# 3_waffling60-MXHS-ISO_mcu.net
KiCad netlist of a schematic drawn in Altium Designer
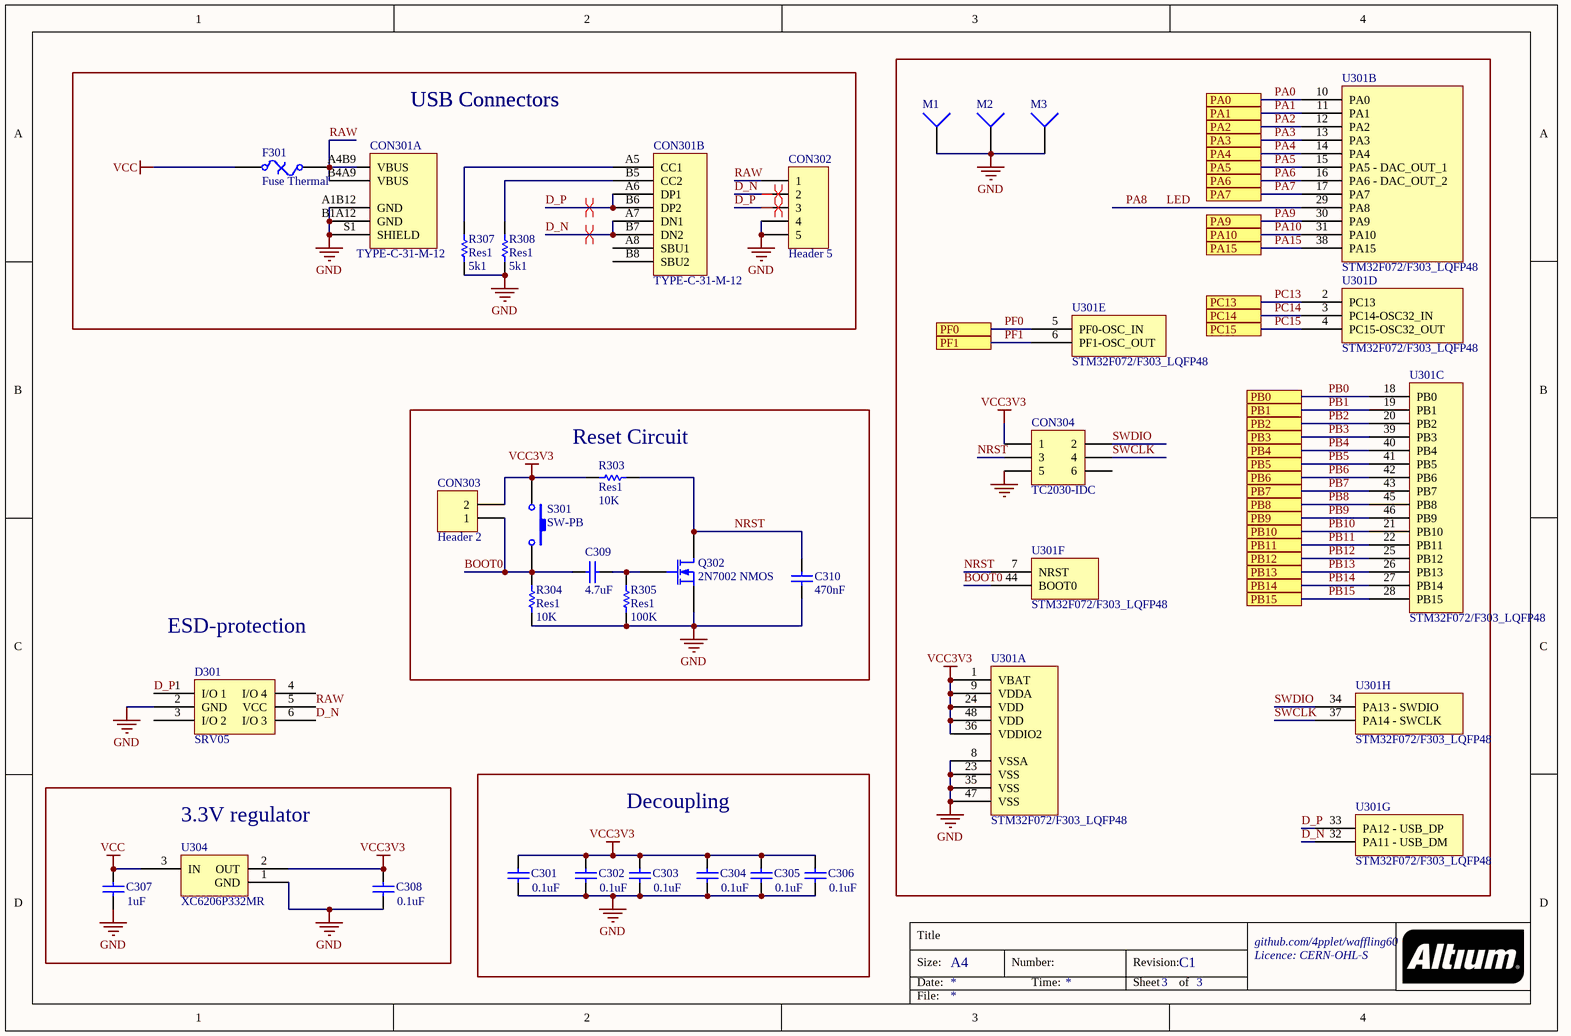
[diagram p0: 3_waffling60-MXHS-ISO_mcu.SchDoc]

(export (version "E")
  (design (tool "Eeschema 10.0.6"))
  (components
    (comp (ref "C301")
      (value "0.1uF")
      (footprint "C0603[1608]")
      (description "Capacitor")
      (fields (field (name "MFG") "KEMET") (field (name "LCSC PART #") "C14663"))
      (libsource (lib "Miscellaneous Devices") (part "Cap"))
    )
    (comp (ref "C302")
      (value "0.1uF")
      (footprint "C0603[1608]")
      (description "Capacitor")
      (fields (field (name "MFG") "KEMET") (field (name "LCSC PART #") "C14663"))
      (libsource (lib "Miscellaneous Devices") (part "Cap"))
    )
    (comp (ref "C303")
      (value "0.1uF")
      (footprint "C0603[1608]")
      (description "Capacitor")
      (fields (field (name "MFG") "KEMET") (field (name "LCSC PART #") "C14663"))
      (libsource (lib "Miscellaneous Devices") (part "Cap"))
    )
    (comp (ref "C304")
      (value "0.1uF")
      (footprint "C0603[1608]")
      (description "Capacitor")
      (fields (field (name "MFG") "KEMET") (field (name "LCSC PART #") "C14663"))
      (libsource (lib "Miscellaneous Devices") (part "Cap"))
    )
    (comp (ref "C305")
      (value "0.1uF")
      (footprint "C0603[1608]")
      (description "Capacitor")
      (fields (field (name "MFG") "KEMET") (field (name "LCSC PART #") "C14663"))
      (libsource (lib "Miscellaneous Devices") (part "Cap"))
    )
    (comp (ref "C306")
      (value "0.1uF")
      (footprint "C0603[1608]")
      (description "Capacitor")
      (fields (field (name "MFG") "KEMET") (field (name "LCSC PART #") "C14663"))
      (libsource (lib "Miscellaneous Devices") (part "Cap"))
    )
    (comp (ref "C307")
      (value "1uF")
      (footprint "C0603[1608]")
      (description "Capacitor")
      (fields (field (name "LCSC PART #") "C15849") (field (name "MRF.PART") "CL10A105KB8NNNC"))
      (libsource (lib "Miscellaneous Devices") (part "Cap"))
    )
    (comp (ref "C308")
      (value "0.1uF")
      (footprint "C0603[1608]")
      (description "Capacitor")
      (fields (field (name "MFG") "KEMET") (field (name "LCSC PART #") "C14663"))
      (libsource (lib "Miscellaneous Devices") (part "Cap"))
    )
    (comp (ref "C309")
      (value "4.7uF")
      (footprint "C0603[1608]")
      (description "Capacitor")
      (fields (field (name "LCSC PART #") "C19666"))
      (libsource (lib "Miscellaneous Devices") (part "Cap"))
    )
    (comp (ref "C310")
      (value "470nF")
      (footprint "C0603[1608]")
      (description "Capacitor")
      (fields (field (name "MFG") "KEMET") (field (name "LCSC PART #") "C14663"))
      (libsource (lib "Miscellaneous Devices") (part "Cap"))
    )
    (comp (ref "CON301")
      (value "TYPE-C-31-M-12")
      (footprint "TYPE-C-31-M-12")
      (fields (field (name "MFG") "Korean Hroparts Elec") (field (name "LCSC PART #") "C165948"))
      (libsource (lib "Schlib1") (part "TYPE-C-31-M-12"))
    )
    (comp (ref "CON302")
      (value "Header 5")
      (footprint "JST SM04B-SRSS-TB")
      (description "JST for USB daughter board")
      (fields (field (name "MFG") "JST Sales America Inc.") (field (name "LCSC PART #") "C160404"))
      (libsource (lib "Miscellaneous Connectors") (part "Header 5"))
    )
    (comp (ref "CON303")
      (value "Header 2")
      (footprint "HDR1X2")
      (description "Header, 2-Pin")
      (libsource (lib "Miscellaneous Connectors") (part "Header 2"))
    )
    (comp (ref "CON304")
      (value "TC2030-IDC")
      (footprint "TC2030-IDC-NL")
      (description "Header, 3-Pin, Dual row")
      (libsource (lib "Miscellaneous Connectors") (part "Header 3X2"))
    )
    (comp (ref "D301")
      (value "SRV05")
      (footprint "SOT-23-6")
      (fields (field (name "LCSC PART #") "C85364") (field (name "MRF.PART") "SRV05-4-P-T7"))
      (libsource (lib "Keebs") (part "SRV05"))
    )
    (comp (ref "F301")
      (value "Fuse Thermal")
      (footprint "C1206[3216]")
      (description "Thermal Fuse")
      (fields (field (name "MFG") "Bel Fuse Inc.") (field (name "LCSC PART #") "C135338"))
      (libsource (lib "Miscellaneous Devices") (part "Fuse Thermal"))
    )
    (comp (ref "M1")
      (value "Socket")
      (footprint "mounting_hole")
      (libsource (lib "Miscellaneous Connectors") (part "Socket"))
    )
    (comp (ref "M2")
      (value "Socket")
      (footprint "mounting_hole")
      (libsource (lib "Miscellaneous Connectors") (part "Socket"))
    )
    (comp (ref "M3")
      (value "Socket")
      (footprint "mounting_hole")
      (libsource (lib "Miscellaneous Connectors") (part "Socket"))
    )
    (comp (ref "Q302")
      (value "2N7002 NMOS")
      (footprint "SOT-23-3")
      (description "N-Channel MOSFET")
      (fields (field (name "LCSC PART #") "C8545") (field (name "MRF.PART") "2N7002"))
      (libsource (lib "Miscellaneous Devices") (part "MOSFET-N"))
    )
    (comp (ref "R303")
      (value "Res1")
      (footprint "R0603[1608]")
      (description "Resistor")
      (fields
        (field (name "ALTIUM_VALUE") "10K")
        (field (name "MFG") "Panasonic Electronic Components")
        (field (name "LCSC PART #") "C25804")
      )
      (libsource (lib "Miscellaneous Devices") (part "Res1"))
    )
    (comp (ref "R304")
      (value "Res1")
      (footprint "R0603[1608]")
      (description "Resistor")
      (fields
        (field (name "ALTIUM_VALUE") "10K")
        (field (name "MFG") "Panasonic Electronic Components")
        (field (name "LCSC PART #") "C25804")
      )
      (libsource (lib "Miscellaneous Devices") (part "Res1"))
    )
    (comp (ref "R305")
      (value "Res1")
      (footprint "R0603[1608]")
      (description "Resistor")
      (fields
        (field (name "ALTIUM_VALUE") "100K")
        (field (name "LCSC PART #") "C25803")
        (field (name "MRF.PART") "0603WAF1003T5E")
      )
      (libsource (lib "Miscellaneous Devices") (part "Res1"))
    )
    (comp (ref "R307")
      (value "Res1")
      (footprint "R0603[1608]")
      (description "Resistor")
      (fields
        (field (name "ALTIUM_VALUE") "5k1")
        (field (name "MFG") "Panasonic Electronic Components")
        (field (name "LCSC PART #") "C23186")
      )
      (libsource (lib "Miscellaneous Devices") (part "Res1"))
    )
    (comp (ref "R308")
      (value "Res1")
      (footprint "R0603[1608]")
      (description "Resistor")
      (fields
        (field (name "ALTIUM_VALUE") "5k1")
        (field (name "MFG") "Panasonic Electronic Components")
        (field (name "LCSC PART #") "C23186")
      )
      (libsource (lib "Miscellaneous Devices") (part "Res1"))
    )
    (comp (ref "S301")
      (value "SW-PB")
      (footprint "XKB Switch")
      (description "Switch")
      (fields (field (name "MFG") "C&K") (field (name "MRF.PART") "TS-1187A-C-D-B"))
      (libsource (lib "Miscellaneous Devices") (part "SW-PB"))
    )
    (comp (ref "U301")
      (value "STM32F072/F303_LQFP48")
      (footprint "STM32 - COMBO 7X7MM")
      (fields (field (name "LCSC PART #") "C915660") (field (name "MRF.PART") "APM32F072CBT6"))
      (libsource (lib "Keebs") (part "STM32F072/F303_LQFP48"))
    )
    (comp (ref "U304")
      (value "XC6206P332MR")
      (footprint "SOT-23-3")
      (fields (field (name "LCSC PART #") "C5446") (field (name "MFG") "Texas Instruments"))
      (libsource (lib "Keebs") (part "SOT23 LDO"))
    )
  )
  (nets
    (net (code "1") (name "/BOOT0") (class "Default")
      (node (ref "C309") (pin "1") (pinfunction "1_1") (pintype "passive"))
      (node (ref "CON303") (pin "1") (pinfunction "1_1") (pintype "passive"))
      (node (ref "R304") (pin "1") (pinfunction "1_1") (pintype "passive"))
      (node (ref "S301") (pin "2") (pinfunction "2_2") (pintype "passive"))
      (node (ref "U301") (pin "44") (pinfunction "BOOT0_44") (pintype "passive"))
    )
    (net (code "2") (name "/D_N") (class "Default")
      (node (ref "CON301") (pin "A7") (pinfunction "DN1_A7") (pintype "passive"))
      (node (ref "CON301") (pin "B7") (pinfunction "DN2_B7") (pintype "passive"))
      (node (ref "CON302") (pin "2") (pinfunction "2_2") (pintype "passive"))
      (node (ref "D301") (pin "6") (pinfunction "I/O_3_6") (pintype "passive"))
      (node (ref "U301") (pin "32") (pinfunction "PA11_-_USB_DM_32") (pintype "passive"))
    )
    (net (code "3") (name "/D_P") (class "Default")
      (node (ref "CON301") (pin "A6") (pinfunction "DP1_A6") (pintype "passive"))
      (node (ref "CON301") (pin "B6") (pinfunction "DP2_B6") (pintype "passive"))
      (node (ref "CON302") (pin "3") (pinfunction "3_3") (pintype "passive"))
      (node (ref "D301") (pin "1") (pinfunction "I/O_1_1") (pintype "passive"))
      (node (ref "U301") (pin "33") (pinfunction "PA12_-_USB_DP_33") (pintype "passive"))
    )
    (net (code "4") (name "/LED") (class "Default")
      (node (ref "U301") (pin "29") (pinfunction "PA8_29") (pintype "passive"))
    )
    (net (code "5") (name "/NRST") (class "Default")
      (node (ref "C310") (pin "1") (pinfunction "1_1") (pintype "passive"))
      (node (ref "CON304") (pin "3") (pinfunction "3_3") (pintype "passive"))
      (node (ref "Q302") (pin "3") (pinfunction "D_3") (pintype "passive"))
      (node (ref "R303") (pin "2") (pinfunction "2_2") (pintype "passive"))
      (node (ref "U301") (pin "7") (pinfunction "NRST_7") (pintype "passive"))
    )
    (net (code "6") (name "/PA0") (class "Default")
      (node (ref "U301") (pin "10") (pinfunction "PA0_10") (pintype "passive"))
    )
    (net (code "7") (name "/PA1") (class "Default")
      (node (ref "U301") (pin "11") (pinfunction "PA1_11") (pintype "passive"))
    )
    (net (code "8") (name "/PA2") (class "Default")
      (node (ref "U301") (pin "12") (pinfunction "PA2_12") (pintype "passive"))
    )
    (net (code "9") (name "/PA3") (class "Default")
      (node (ref "U301") (pin "13") (pinfunction "PA3_13") (pintype "passive"))
    )
    (net (code "10") (name "/PA4") (class "Default")
      (node (ref "U301") (pin "14") (pinfunction "PA4_14") (pintype "passive"))
    )
    (net (code "11") (name "/PA5") (class "Default")
      (node (ref "U301") (pin "15") (pinfunction "PA5_-_DAC_OUT_1_15") (pintype "passive"))
    )
    (net (code "12") (name "/PA6") (class "Default")
      (node (ref "U301") (pin "16") (pinfunction "PA6_-_DAC_OUT_2_16") (pintype "passive"))
    )
    (net (code "13") (name "/PA7") (class "Default")
      (node (ref "U301") (pin "17") (pinfunction "PA7_17") (pintype "passive"))
    )
    (net (code "14") (name "/PA9") (class "Default")
      (node (ref "U301") (pin "30") (pinfunction "PA9_30") (pintype "passive"))
    )
    (net (code "15") (name "/PA10") (class "Default")
      (node (ref "U301") (pin "31") (pinfunction "PA10_31") (pintype "passive"))
    )
    (net (code "16") (name "/PA15") (class "Default")
      (node (ref "U301") (pin "38") (pinfunction "PA15_38") (pintype "passive"))
    )
    (net (code "17") (name "/PB0") (class "Default")
      (node (ref "U301") (pin "18") (pinfunction "PB0_18") (pintype "passive"))
    )
    (net (code "18") (name "/PB1") (class "Default")
      (node (ref "U301") (pin "19") (pinfunction "PB1_19") (pintype "passive"))
    )
    (net (code "19") (name "/PB2") (class "Default")
      (node (ref "U301") (pin "20") (pinfunction "PB2_20") (pintype "passive"))
    )
    (net (code "20") (name "/PB3") (class "Default")
      (node (ref "U301") (pin "39") (pinfunction "PB3_39") (pintype "passive"))
    )
    (net (code "21") (name "/PB4") (class "Default")
      (node (ref "U301") (pin "40") (pinfunction "PB4_40") (pintype "passive"))
    )
    (net (code "22") (name "/PB5") (class "Default")
      (node (ref "U301") (pin "41") (pinfunction "PB5_41") (pintype "passive"))
    )
    (net (code "23") (name "/PB6") (class "Default")
      (node (ref "U301") (pin "42") (pinfunction "PB6_42") (pintype "passive"))
    )
    (net (code "24") (name "/PB7") (class "Default")
      (node (ref "U301") (pin "43") (pinfunction "PB7_43") (pintype "passive"))
    )
    (net (code "25") (name "/PB8") (class "Default")
      (node (ref "U301") (pin "45") (pinfunction "PB8_45") (pintype "passive"))
    )
    (net (code "26") (name "/PB9") (class "Default")
      (node (ref "U301") (pin "46") (pinfunction "PB9_46") (pintype "passive"))
    )
    (net (code "27") (name "/PB10") (class "Default")
      (node (ref "U301") (pin "21") (pinfunction "PB10_21") (pintype "passive"))
    )
    (net (code "28") (name "/PB11") (class "Default")
      (node (ref "U301") (pin "22") (pinfunction "PB11_22") (pintype "passive"))
    )
    (net (code "29") (name "/PB12") (class "Default")
      (node (ref "U301") (pin "25") (pinfunction "PB12_25") (pintype "passive"))
    )
    (net (code "30") (name "/PB13") (class "Default")
      (node (ref "U301") (pin "26") (pinfunction "PB13_26") (pintype "passive"))
    )
    (net (code "31") (name "/PB14") (class "Default")
      (node (ref "U301") (pin "27") (pinfunction "PB14_27") (pintype "passive"))
    )
    (net (code "32") (name "/PB15") (class "Default")
      (node (ref "U301") (pin "28") (pinfunction "PB15_28") (pintype "passive"))
    )
    (net (code "33") (name "/PC13") (class "Default")
      (node (ref "U301") (pin "2") (pinfunction "PC13_2") (pintype "passive"))
    )
    (net (code "34") (name "/PC14") (class "Default")
      (node (ref "U301") (pin "3") (pinfunction "PC14-OSC32_IN_3") (pintype "passive"))
    )
    (net (code "35") (name "/PC15") (class "Default")
      (node (ref "U301") (pin "4") (pinfunction "PC15-OSC32_OUT_4") (pintype "passive"))
    )
    (net (code "36") (name "/PF0") (class "Default")
      (node (ref "U301") (pin "5") (pinfunction "PF0-OSC_IN_5") (pintype "passive"))
    )
    (net (code "37") (name "/PF1") (class "Default")
      (node (ref "U301") (pin "6") (pinfunction "PF1-OSC_OUT_6") (pintype "passive"))
    )
    (net (code "38") (name "/RAW") (class "Default")
      (node (ref "CON301") (pin "A4B9") (pinfunction "VBUS_A4B9") (pintype "passive"))
      (node (ref "CON301") (pin "B4A9") (pinfunction "VBUS_B4A9") (pintype "passive"))
      (node (ref "CON302") (pin "1") (pinfunction "1_1") (pintype "passive"))
      (node (ref "D301") (pin "5") (pinfunction "VCC_5") (pintype "passive"))
      (node (ref "F301") (pin "2") (pinfunction "2_2") (pintype "passive"))
    )
    (net (code "39") (name "/SWCLK") (class "Default")
      (node (ref "CON304") (pin "4") (pinfunction "4_4") (pintype "passive"))
      (node (ref "U301") (pin "37") (pinfunction "PA14_-_SWCLK_37") (pintype "passive"))
    )
    (net (code "40") (name "/SWDIO") (class "Default")
      (node (ref "CON304") (pin "2") (pinfunction "2_2") (pintype "passive"))
      (node (ref "U301") (pin "34") (pinfunction "PA13_-_SWDIO_34") (pintype "passive"))
    )
    (net (code "41") (name "GND") (class "Default")
      (node (ref "C301") (pin "1") (pinfunction "1_1") (pintype "passive"))
      (node (ref "C302") (pin "1") (pinfunction "1_1") (pintype "passive"))
      (node (ref "C303") (pin "1") (pinfunction "1_1") (pintype "passive"))
      (node (ref "C304") (pin "1") (pinfunction "1_1") (pintype "passive"))
      (node (ref "C305") (pin "1") (pinfunction "1_1") (pintype "passive"))
      (node (ref "C306") (pin "1") (pinfunction "1_1") (pintype "passive"))
      (node (ref "C307") (pin "1") (pinfunction "1_1") (pintype "passive"))
      (node (ref "C308") (pin "1") (pinfunction "1_1") (pintype "passive"))
      (node (ref "C310") (pin "2") (pinfunction "2_2") (pintype "passive"))
      (node (ref "CON301") (pin "A1B12") (pinfunction "GND_A1B12") (pintype "passive"))
      (node (ref "CON301") (pin "B1A12") (pinfunction "GND_B1A12") (pintype "passive"))
      (node (ref "CON301") (pin "S1") (pinfunction "SHIELD_S1") (pintype "passive"))
      (node (ref "CON302") (pin "4") (pinfunction "4_4") (pintype "passive"))
      (node (ref "CON302") (pin "5") (pinfunction "5_5") (pintype "passive"))
      (node (ref "CON304") (pin "5") (pinfunction "5_5") (pintype "passive"))
      (node (ref "D301") (pin "2") (pinfunction "GND_2") (pintype "passive"))
      (node (ref "M1") (pin "1") (pinfunction "1_1") (pintype "passive"))
      (node (ref "M2") (pin "1") (pinfunction "1_1") (pintype "passive"))
      (node (ref "M3") (pin "1") (pinfunction "1_1") (pintype "passive"))
      (node (ref "Q302") (pin "2") (pinfunction "S_2") (pintype "passive"))
      (node (ref "R304") (pin "2") (pinfunction "2_2") (pintype "passive"))
      (node (ref "R305") (pin "2") (pinfunction "2_2") (pintype "passive"))
      (node (ref "R307") (pin "2") (pinfunction "2_2") (pintype "passive"))
      (node (ref "R308") (pin "2") (pinfunction "2_2") (pintype "passive"))
      (node (ref "U301") (pin "23") (pinfunction "VSS_23") (pintype "passive"))
      (node (ref "U301") (pin "35") (pinfunction "VSS_35") (pintype "passive"))
      (node (ref "U301") (pin "47") (pinfunction "VSS_47") (pintype "passive"))
      (node (ref "U301") (pin "8") (pinfunction "VSSA_8") (pintype "passive"))
      (node (ref "U304") (pin "1") (pinfunction "GND_1") (pintype "passive"))
    )
    (net (code "42") (name "Net-(CON301B-CC1)") (class "Default")
      (node (ref "CON301") (pin "A5") (pinfunction "CC1_A5") (pintype "passive"))
      (node (ref "R307") (pin "1") (pinfunction "1_1") (pintype "passive"))
    )
    (net (code "43") (name "Net-(CON301B-CC2)") (class "Default")
      (node (ref "CON301") (pin "B5") (pinfunction "CC2_B5") (pintype "passive"))
      (node (ref "R308") (pin "1") (pinfunction "1_1") (pintype "passive"))
    )
    (net (code "44") (name "Net-(Q302-G)") (class "Default")
      (node (ref "C309") (pin "2") (pinfunction "2_2") (pintype "passive"))
      (node (ref "Q302") (pin "1") (pinfunction "G_1") (pintype "passive"))
      (node (ref "R305") (pin "1") (pinfunction "1_1") (pintype "passive"))
    )
    (net (code "45") (name "VCC") (class "Default")
      (node (ref "C307") (pin "2") (pinfunction "2_2") (pintype "passive"))
      (node (ref "F301") (pin "1") (pinfunction "1_1") (pintype "passive"))
      (node (ref "U304") (pin "3") (pinfunction "IN_3") (pintype "passive"))
    )
    (net (code "46") (name "VCC3V3") (class "Default")
      (node (ref "C301") (pin "2") (pinfunction "2_2") (pintype "passive"))
      (node (ref "C302") (pin "2") (pinfunction "2_2") (pintype "passive"))
      (node (ref "C303") (pin "2") (pinfunction "2_2") (pintype "passive"))
      (node (ref "C304") (pin "2") (pinfunction "2_2") (pintype "passive"))
      (node (ref "C305") (pin "2") (pinfunction "2_2") (pintype "passive"))
      (node (ref "C306") (pin "2") (pinfunction "2_2") (pintype "passive"))
      (node (ref "C308") (pin "2") (pinfunction "2_2") (pintype "passive"))
      (node (ref "CON303") (pin "2") (pinfunction "2_2") (pintype "passive"))
      (node (ref "CON304") (pin "1") (pinfunction "1_1") (pintype "passive"))
      (node (ref "R303") (pin "1") (pinfunction "1_1") (pintype "passive"))
      (node (ref "S301") (pin "1") (pinfunction "1_1") (pintype "passive"))
      (node (ref "U301") (pin "1") (pinfunction "VBAT_1") (pintype "passive"))
      (node (ref "U301") (pin "24") (pinfunction "VDD_24") (pintype "passive"))
      (node (ref "U301") (pin "36") (pinfunction "VDDIO2_36") (pintype "passive"))
      (node (ref "U301") (pin "48") (pinfunction "VDD_48") (pintype "passive"))
      (node (ref "U301") (pin "9") (pinfunction "VDDA_9") (pintype "passive"))
      (node (ref "U304") (pin "2") (pinfunction "OUT_2") (pintype "passive"))
    )
    (net (code "47") (name "unconnected-(CON301B-SBU1-PadA8)") (class "Default")
      (node (ref "CON301") (pin "A8") (pinfunction "SBU1_A8") (pintype "passive"))
    )
    (net (code "48") (name "unconnected-(CON301B-SBU2-PadB8)") (class "Default")
      (node (ref "CON301") (pin "B8") (pinfunction "SBU2_B8") (pintype "passive"))
    )
    (net (code "49") (name "unconnected-(CON304-Pad6)") (class "Default")
      (node (ref "CON304") (pin "6") (pinfunction "6_6") (pintype "passive"))
    )
    (net (code "50") (name "unconnected-(D301-I{slash}O_2-Pad3)") (class "Default")
      (node (ref "D301") (pin "3") (pinfunction "I/O_2_3") (pintype "passive"))
    )
    (net (code "51") (name "unconnected-(D301-I{slash}O_4-Pad4)") (class "Default")
      (node (ref "D301") (pin "4") (pinfunction "I/O_4_4") (pintype "passive"))
    )
  )
)
